# AD9834.net
KiCad netlist of a schematic drawn in Altium Designer
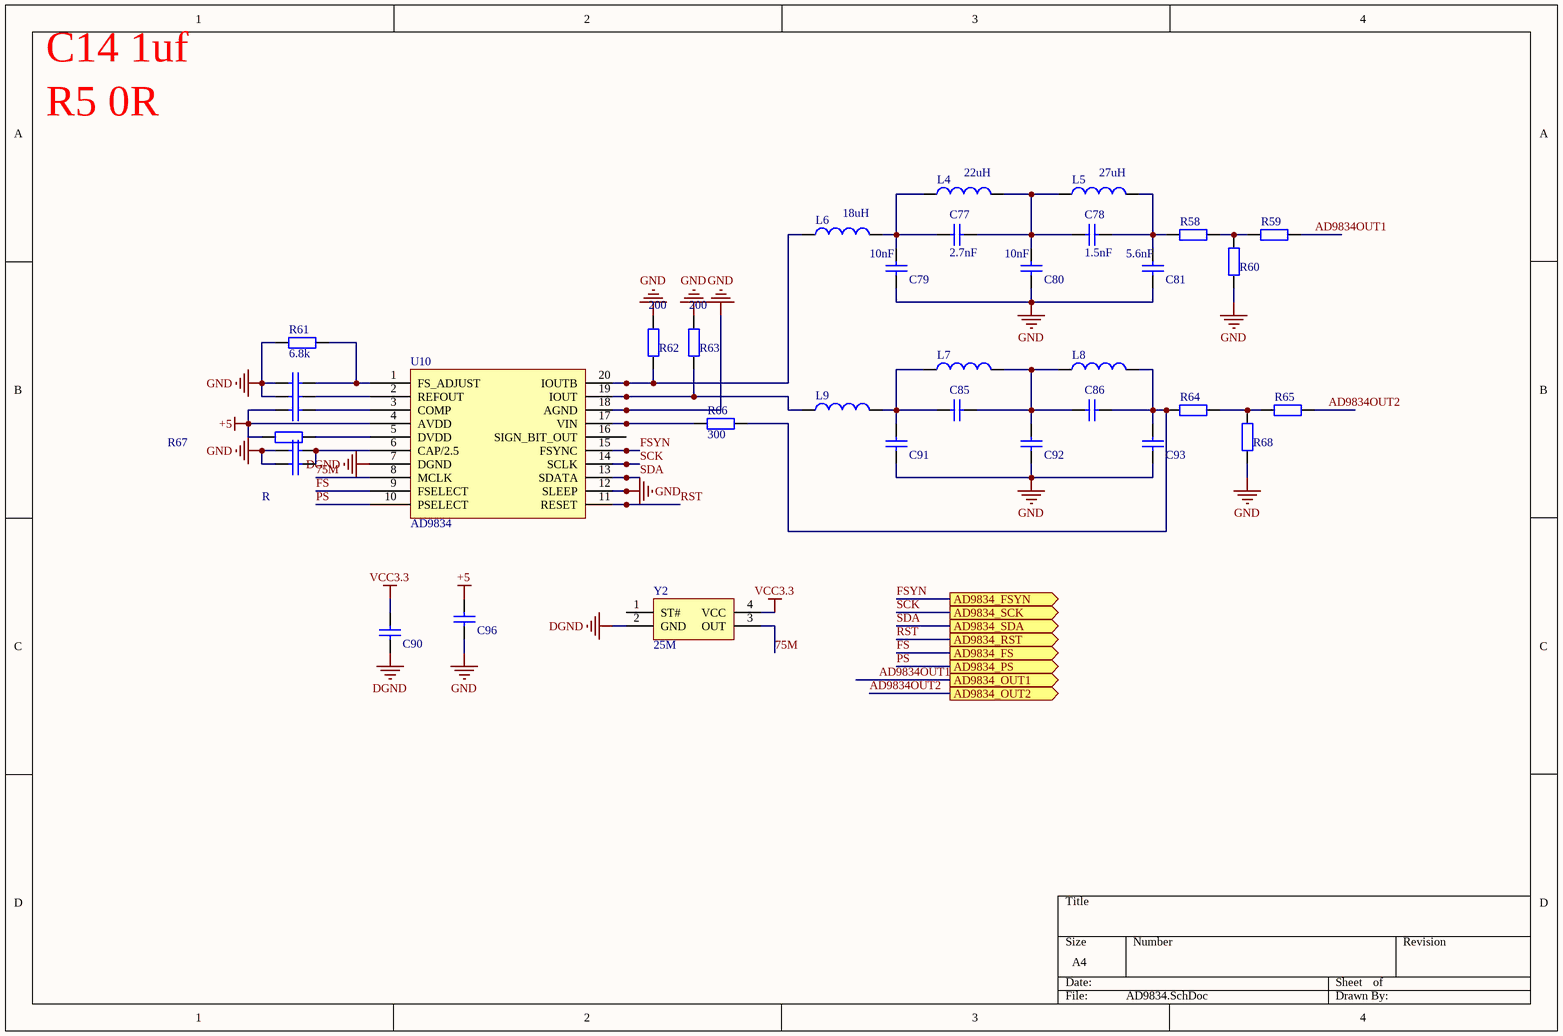
[diagram p0: AD9834.SchDoc]

(export (version "E")
  (design (tool "Eeschema 10.0.6"))
  (components
    (comp (ref "C77")
      (value "2.7nF")
      (footprint "0603_C")
      (description "贴片电容")
      (libsource (lib "JLC") (part "0603 10nF (103) 10% 50V"))
    )
    (comp (ref "C78")
      (value "1.5nF")
      (footprint "0603_C")
      (description "贴片电容")
      (libsource (lib "JLC") (part "0603 10nF (103) 10% 50V"))
    )
    (comp (ref "C79")
      (value "10nF")
      (footprint "0603_C")
      (description "贴片电容")
      (libsource (lib "JLC") (part "0603 10nF (103) 10% 50V"))
    )
    (comp (ref "C80")
      (value "10nF")
      (footprint "0603_C")
      (description "贴片电容")
      (libsource (lib "JLC") (part "0603 10nF (103) 10% 50V"))
    )
    (comp (ref "C81")
      (value "5.6nF")
      (footprint "0603_C")
      (description "贴片电容")
      (libsource (lib "JLC") (part "0603 10nF (103) 10% 50V"))
    )
    (comp (ref "C82")
      (value "10nF (103) 10% 50V")
      (footprint "0603_C")
      (description "贴片电容")
      (libsource (lib "JLC") (part "0603 10nF (103) 10% 50V"))
    )
    (comp (ref "C83")
      (value "10nF (103) 10% 50V")
      (footprint "0603_C")
      (description "贴片电容")
      (libsource (lib "JLC") (part "0603 10nF (103) 10% 50V"))
    )
    (comp (ref "C84")
      (value "10nF (103) 10% 50V")
      (footprint "0603_C")
      (description "贴片电容")
      (libsource (lib "JLC") (part "0603 10nF (103) 10% 50V"))
    )
    (comp (ref "C85")
      (value "10nF (103) 10% 50V")
      (footprint "0603_C")
      (description "贴片电容")
      (libsource (lib "JLC") (part "0603 10nF (103) 10% 50V"))
    )
    (comp (ref "C86")
      (value "10nF (103) 10% 50V")
      (footprint "0603_C")
      (description "贴片电容")
      (libsource (lib "JLC") (part "0603 10nF (103) 10% 50V"))
    )
    (comp (ref "C87")
      (value "10nF (103) 10% 50V")
      (footprint "0603_C")
      (description "贴片电容")
      (libsource (lib "JLC") (part "0603 10nF (103) 10% 50V"))
    )
    (comp (ref "C89")
      (value "10nF (103) 10% 50V")
      (footprint "0603_C")
      (description "贴片电容")
      (libsource (lib "JLC") (part "0603 10nF (103) 10% 50V"))
    )
    (comp (ref "C90")
      (value "10nF (103) 10% 50V")
      (footprint "0603_C")
      (description "贴片电容")
      (libsource (lib "JLC") (part "0603 10nF (103) 10% 50V"))
    )
    (comp (ref "C91")
      (value "10nF (103) 10% 50V")
      (footprint "0603_C")
      (description "贴片电容")
      (libsource (lib "JLC") (part "0603 10nF (103) 10% 50V"))
    )
    (comp (ref "C92")
      (value "10nF (103) 10% 50V")
      (footprint "0603_C")
      (description "贴片电容")
      (libsource (lib "JLC") (part "0603 10nF (103) 10% 50V"))
    )
    (comp (ref "C93")
      (value "10nF (103) 10% 50V")
      (footprint "0603_C")
      (description "贴片电容")
      (libsource (lib "JLC") (part "0603 10nF (103) 10% 50V"))
    )
    (comp (ref "C96")
      (value "10nF (103) 10% 50V")
      (footprint "0603_C")
      (description "贴片电容")
      (libsource (lib "JLC") (part "0603 10nF (103) 10% 50V"))
    )
    (comp (ref "L4")
      (value "22uH")
      (footprint "0603_L")
      (description "Inductor")
      (fields (field (name "PUBLISHER") "Altium Limited"))
      (libsource (lib "Miscellaneous Devices") (part "Inductor"))
    )
    (comp (ref "L5")
      (value "27uH")
      (footprint "0603_L")
      (description "Inductor")
      (fields (field (name "PUBLISHER") "Altium Limited"))
      (libsource (lib "Miscellaneous Devices") (part "Inductor"))
    )
    (comp (ref "L6")
      (value "18uH")
      (footprint "0603_L")
      (description "Inductor")
      (fields (field (name "PUBLISHER") "Altium Limited"))
      (libsource (lib "Miscellaneous Devices") (part "Inductor"))
    )
    (comp (ref "L7")
      (value "699.1nH")
      (footprint "0603_L")
      (description "Inductor")
      (fields (field (name "PUBLISHER") "Altium Limited"))
      (libsource (lib "Miscellaneous Devices") (part "Inductor"))
    )
    (comp (ref "L8")
      (value "596.4nH")
      (footprint "0603_L")
      (description "Inductor")
      (fields (field (name "PUBLISHER") "Altium Limited"))
      (libsource (lib "Miscellaneous Devices") (part "Inductor"))
    )
    (comp (ref "L9")
      (value "22uH")
      (footprint "0603_L")
      (description "Inductor")
      (fields (field (name "PUBLISHER") "Altium Limited"))
      (libsource (lib "Miscellaneous Devices") (part "Inductor"))
    )
    (comp (ref "R58")
      (value "110Ω (1100) ±1%")
      (footprint "0603_R")
      (description "贴片电阻")
      (libsource (lib "") (part "0603 110Ω (1100) 1%_1"))
    )
    (comp (ref "R59")
      (value "110Ω (1100) ±1%")
      (footprint "0603_R")
      (description "贴片电阻")
      (libsource (lib "") (part "0603 110Ω (1100) 1%_1"))
    )
    (comp (ref "R60")
      (value "110Ω (1100) ±1%")
      (footprint "0603_R")
      (description "贴片电阻")
      (libsource (lib "JLC") (part "0603 110Ω (1100) 1%"))
    )
    (comp (ref "R61")
      (value "6.8k")
      (footprint "0603_R")
      (description "贴片电阻")
      (libsource (lib "") (part "0603 110Ω (1100) 1%_2"))
    )
    (comp (ref "R62")
      (value "200")
      (footprint "0603_R")
      (description "贴片电阻")
      (libsource (lib "JLC") (part "0603 110Ω (1100) 1%"))
    )
    (comp (ref "R63")
      (value "200")
      (footprint "0603_R")
      (description "贴片电阻")
      (libsource (lib "JLC") (part "0603 110Ω (1100) 1%"))
    )
    (comp (ref "R64")
      (value "110Ω (1100) ±1%")
      (footprint "0603_R")
      (description "贴片电阻")
      (libsource (lib "") (part "0603 110Ω (1100) 1%_1"))
    )
    (comp (ref "R65")
      (value "110Ω (1100) ±1%")
      (footprint "0603_R")
      (description "贴片电阻")
      (libsource (lib "") (part "0603 110Ω (1100) 1%_1"))
    )
    (comp (ref "R66")
      (value "300")
      (footprint "0603_R")
      (description "贴片电阻")
      (libsource (lib "") (part "0603 110Ω (1100) 1%_1"))
    )
    (comp (ref "R67") (value "R") (footprint "R_0603") (libsource (lib "cooperation") (part "Res")))
    (comp (ref "R68")
      (value "110Ω (1100) ±1%")
      (footprint "0603_R")
      (description "贴片电阻")
      (libsource (lib "JLC") (part "0603 110Ω (1100) 1%"))
    )
    (comp (ref "U10")
      (value "AD9834")
      (footprint "TSSOP20_N")
      (libsource (lib "Cooperation") (part "AD9834"))
    )
    (comp (ref "Y2")
      (value "25M")
      (footprint "OSC 3225-4P")
      (fields (field (name "Comment") "CRYSTAL"))
      (libsource (lib "Cooperation") (part "CRYSTAL_有源晶振-25M-3225-4P"))
    )
  )
  (nets
    (net (code "1") (name "+5") (class "Default")
      (node (ref "C84") (pin "1") (pinfunction "1_1") (pintype "passive"))
      (node (ref "C96") (pin "2") (pinfunction "2_2") (pintype "passive"))
      (node (ref "R67") (pin "1") (pinfunction "1_1") (pintype "passive"))
      (node (ref "U10") (pin "4") (pinfunction "AVDD_4") (pintype "passive"))
    )
    (net (code "2") (name "/75M") (class "Default")
      (node (ref "U10") (pin "8") (pinfunction "MCLK_8") (pintype "passive"))
      (node (ref "Y2") (pin "3") (pinfunction "OUT_3") (pintype "passive"))
    )
    (net (code "3") (name "/AD9834OUT1") (class "Default")
      (node (ref "R59") (pin "2") (pinfunction "2_2") (pintype "passive"))
    )
    (net (code "4") (name "/AD9834OUT2") (class "Default")
      (node (ref "R65") (pin "2") (pinfunction "2_2") (pintype "passive"))
    )
    (net (code "5") (name "/FS") (class "Default")
      (node (ref "U10") (pin "9") (pinfunction "FSELECT_9") (pintype "passive"))
    )
    (net (code "6") (name "/FSYN") (class "Default")
      (node (ref "U10") (pin "15") (pinfunction "FSYNC_15") (pintype "passive"))
    )
    (net (code "7") (name "/PS") (class "Default")
      (node (ref "U10") (pin "10") (pinfunction "PSELECT_10") (pintype "passive"))
    )
    (net (code "8") (name "/RST") (class "Default")
      (node (ref "U10") (pin "11") (pinfunction "RESET_11") (pintype "passive"))
    )
    (net (code "9") (name "/SCK") (class "Default")
      (node (ref "U10") (pin "14") (pinfunction "SCLK_14") (pintype "passive"))
    )
    (net (code "10") (name "/SDA") (class "Default")
      (node (ref "U10") (pin "13") (pinfunction "SDATA_13") (pintype "passive"))
    )
    (net (code "11") (name "DGND") (class "Default")
      (node (ref "C90") (pin "1") (pinfunction "1_1") (pintype "passive"))
      (node (ref "U10") (pin "7") (pinfunction "DGND_7") (pintype "passive"))
      (node (ref "Y2") (pin "2") (pinfunction "GND_2") (pintype "passive"))
    )
    (net (code "12") (name "GND") (class "Default")
      (node (ref "C79") (pin "1") (pinfunction "1_1") (pintype "passive"))
      (node (ref "C80") (pin "1") (pinfunction "1_1") (pintype "passive"))
      (node (ref "C81") (pin "1") (pinfunction "1_1") (pintype "passive"))
      (node (ref "C82") (pin "1") (pinfunction "1_1") (pintype "passive"))
      (node (ref "C83") (pin "1") (pinfunction "1_1") (pintype "passive"))
      (node (ref "C87") (pin "1") (pinfunction "1_1") (pintype "passive"))
      (node (ref "C89") (pin "1") (pinfunction "1_1") (pintype "passive"))
      (node (ref "C91") (pin "1") (pinfunction "1_1") (pintype "passive"))
      (node (ref "C92") (pin "1") (pinfunction "1_1") (pintype "passive"))
      (node (ref "C93") (pin "1") (pinfunction "1_1") (pintype "passive"))
      (node (ref "C96") (pin "1") (pinfunction "1_1") (pintype "passive"))
      (node (ref "R60") (pin "1") (pinfunction "1_1") (pintype "passive"))
      (node (ref "R61") (pin "2") (pinfunction "2_2") (pintype "passive"))
      (node (ref "R62") (pin "2") (pinfunction "2_2") (pintype "passive"))
      (node (ref "R63") (pin "2") (pinfunction "2_2") (pintype "passive"))
      (node (ref "R68") (pin "1") (pinfunction "1_1") (pintype "passive"))
      (node (ref "U10") (pin "12") (pinfunction "SLEEP_12") (pintype "passive"))
      (node (ref "U10") (pin "18") (pinfunction "AGND_18") (pintype "passive"))
    )
    (net (code "13") (name "Net-(C77-Pad1)") (class "Default")
      (node (ref "C77") (pin "1") (pinfunction "1_1") (pintype "passive"))
      (node (ref "C79") (pin "2") (pinfunction "2_2") (pintype "passive"))
      (node (ref "L4") (pin "1") (pinfunction "1_1") (pintype "passive"))
      (node (ref "L6") (pin "2") (pinfunction "2_2") (pintype "passive"))
    )
    (net (code "14") (name "Net-(C77-Pad2)") (class "Default")
      (node (ref "C77") (pin "2") (pinfunction "2_2") (pintype "passive"))
      (node (ref "C78") (pin "1") (pinfunction "1_1") (pintype "passive"))
      (node (ref "C80") (pin "2") (pinfunction "2_2") (pintype "passive"))
      (node (ref "L4") (pin "2") (pinfunction "2_2") (pintype "passive"))
      (node (ref "L5") (pin "1") (pinfunction "1_1") (pintype "passive"))
    )
    (net (code "15") (name "Net-(C78-Pad2)") (class "Default")
      (node (ref "C78") (pin "2") (pinfunction "2_2") (pintype "passive"))
      (node (ref "C81") (pin "2") (pinfunction "2_2") (pintype "passive"))
      (node (ref "L5") (pin "2") (pinfunction "2_2") (pintype "passive"))
      (node (ref "R58") (pin "1") (pinfunction "1_1") (pintype "passive"))
    )
    (net (code "16") (name "Net-(C85-Pad1)") (class "Default")
      (node (ref "C85") (pin "1") (pinfunction "1_1") (pintype "passive"))
      (node (ref "C91") (pin "2") (pinfunction "2_2") (pintype "passive"))
      (node (ref "L7") (pin "1") (pinfunction "1_1") (pintype "passive"))
      (node (ref "L9") (pin "2") (pinfunction "2_2") (pintype "passive"))
    )
    (net (code "17") (name "Net-(C85-Pad2)") (class "Default")
      (node (ref "C85") (pin "2") (pinfunction "2_2") (pintype "passive"))
      (node (ref "C86") (pin "1") (pinfunction "1_1") (pintype "passive"))
      (node (ref "C92") (pin "2") (pinfunction "2_2") (pintype "passive"))
      (node (ref "L7") (pin "2") (pinfunction "2_2") (pintype "passive"))
      (node (ref "L8") (pin "1") (pinfunction "1_1") (pintype "passive"))
    )
    (net (code "18") (name "Net-(C86-Pad2)") (class "Default")
      (node (ref "C86") (pin "2") (pinfunction "2_2") (pintype "passive"))
      (node (ref "C93") (pin "2") (pinfunction "2_2") (pintype "passive"))
      (node (ref "L8") (pin "2") (pinfunction "2_2") (pintype "passive"))
      (node (ref "R64") (pin "1") (pinfunction "1_1") (pintype "passive"))
      (node (ref "R66") (pin "2") (pinfunction "2_2") (pintype "passive"))
    )
    (net (code "19") (name "Net-(R58-Pad2)") (class "Default")
      (node (ref "R58") (pin "2") (pinfunction "2_2") (pintype "passive"))
      (node (ref "R59") (pin "1") (pinfunction "1_1") (pintype "passive"))
      (node (ref "R60") (pin "2") (pinfunction "2_2") (pintype "passive"))
    )
    (net (code "20") (name "Net-(R64-Pad2)") (class "Default")
      (node (ref "R64") (pin "2") (pinfunction "2_2") (pintype "passive"))
      (node (ref "R65") (pin "1") (pinfunction "1_1") (pintype "passive"))
      (node (ref "R68") (pin "2") (pinfunction "2_2") (pintype "passive"))
    )
    (net (code "21") (name "Net-(U10-CAP{slash}2.5)") (class "Default")
      (node (ref "C87") (pin "2") (pinfunction "2_2") (pintype "passive"))
      (node (ref "C89") (pin "2") (pinfunction "2_2") (pintype "passive"))
      (node (ref "U10") (pin "6") (pinfunction "CAP/2.5_6") (pintype "passive"))
    )
    (net (code "22") (name "Net-(U10-COMP)") (class "Default")
      (node (ref "C84") (pin "2") (pinfunction "2_2") (pintype "passive"))
      (node (ref "U10") (pin "3") (pinfunction "COMP_3") (pintype "passive"))
    )
    (net (code "23") (name "Net-(U10-DVDD)") (class "Default")
      (node (ref "R67") (pin "2") (pinfunction "2_2") (pintype "passive"))
      (node (ref "U10") (pin "5") (pinfunction "DVDD_5") (pintype "passive"))
    )
    (net (code "24") (name "Net-(U10-FS_ADJUST)") (class "Default")
      (node (ref "C82") (pin "2") (pinfunction "2_2") (pintype "passive"))
      (node (ref "R61") (pin "1") (pinfunction "1_1") (pintype "passive"))
      (node (ref "U10") (pin "1") (pinfunction "FS_ADJUST_1") (pintype "passive"))
    )
    (net (code "25") (name "Net-(U10-IOUT)") (class "Default")
      (node (ref "L9") (pin "1") (pinfunction "1_1") (pintype "passive"))
      (node (ref "R63") (pin "1") (pinfunction "1_1") (pintype "passive"))
      (node (ref "U10") (pin "19") (pinfunction "IOUT_19") (pintype "passive"))
    )
    (net (code "26") (name "Net-(U10-IOUTB)") (class "Default")
      (node (ref "L6") (pin "1") (pinfunction "1_1") (pintype "passive"))
      (node (ref "R62") (pin "1") (pinfunction "1_1") (pintype "passive"))
      (node (ref "U10") (pin "20") (pinfunction "IOUTB_20") (pintype "passive"))
    )
    (net (code "27") (name "Net-(U10-REFOUT)") (class "Default")
      (node (ref "C83") (pin "2") (pinfunction "2_2") (pintype "passive"))
      (node (ref "U10") (pin "2") (pinfunction "REFOUT_2") (pintype "passive"))
    )
    (net (code "28") (name "Net-(U10-VIN)") (class "Default")
      (node (ref "R66") (pin "1") (pinfunction "1_1") (pintype "passive"))
      (node (ref "U10") (pin "17") (pinfunction "VIN_17") (pintype "passive"))
    )
    (net (code "29") (name "VCC3.3") (class "Default")
      (node (ref "C90") (pin "2") (pinfunction "2_2") (pintype "passive"))
      (node (ref "Y2") (pin "4") (pinfunction "VCC_4") (pintype "passive"))
    )
    (net (code "30") (name "unconnected-(U10-SIGN_BIT_OUT-Pad16)") (class "Default")
      (node (ref "U10") (pin "16") (pinfunction "SIGN_BIT_OUT_16") (pintype "passive"))
    )
    (net (code "31") (name "unconnected-(Y2-ST#-Pad1)") (class "Default")
      (node (ref "Y2") (pin "1") (pinfunction "ST#_1") (pintype "passive"))
    )
  )
)
